# Power_supply_LED.net
KiCad netlist of a schematic drawn in Altium Designer
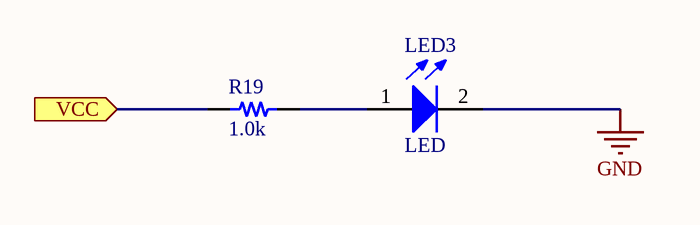
[diagram p0: Power_supply_LED.SchDoc]

(export (version "E")
  (design (tool "Eeschema 10.0.6"))
  (components
    (comp (ref "LED3") (value "LED") (footprint "0805_LED") (libsource (lib "Altium-Lib") (part "LED")))
    (comp (ref "R19")
      (value "1.0k")
      (footprint "RES 0805/2012")
      (fields
        (field (name "TOLERANCE") "10%")
        (field (name "POWER") "1/10W")
        (field (name "Comment") "Resistor 1.0k 0805 1/10W 10%")
        (field (name "CREATED_BY") "Nick Mah")
      )
      (libsource (lib "Altium-Lib") (part "Resistor"))
    )
  )
  (nets
    (net (code "1") (name "/VCC") (class "Default")
      (node (ref "R19") (pin "1") (pinfunction "1_1") (pintype "passive"))
    )
    (net (code "2") (name "GND") (class "Default")
      (node (ref "LED3") (pin "2") (pinfunction "K_2") (pintype "passive"))
    )
    (net (code "3") (name "Net-(LED3-A)") (class "Default")
      (node (ref "LED3") (pin "1") (pinfunction "A_1") (pintype "passive"))
      (node (ref "R19") (pin "2") (pinfunction "2_2") (pintype "passive"))
    )
  )
)
